# Sheet1.net
KiCad netlist of a schematic drawn in Altium Designer
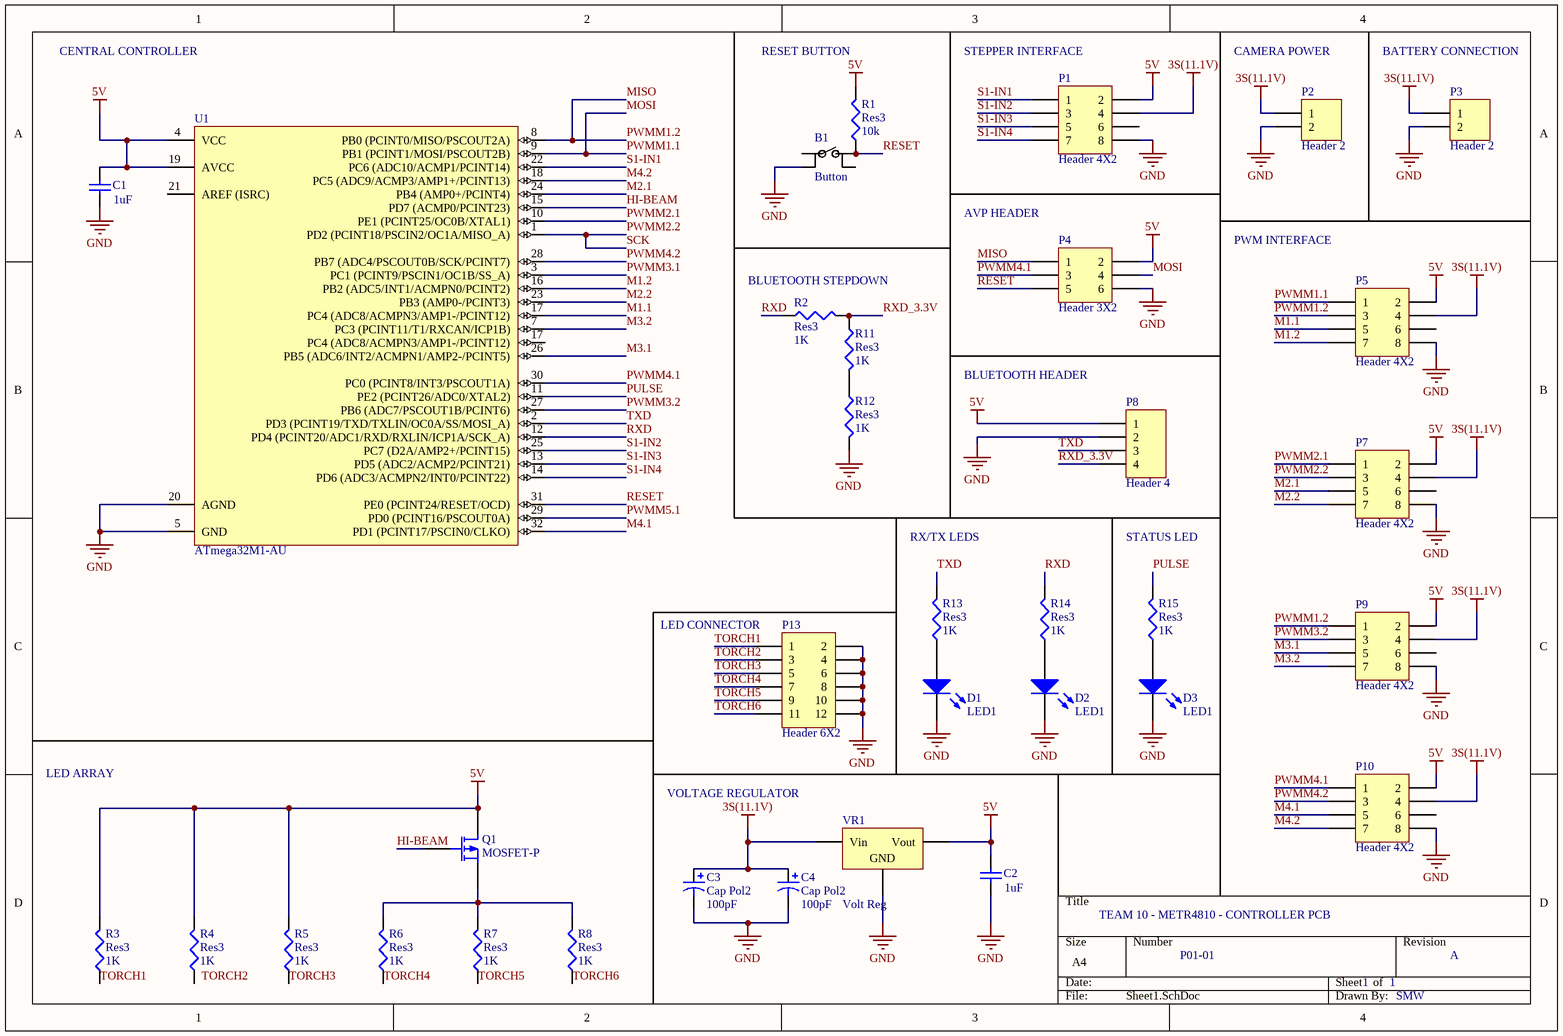
[diagram p0: Sheet1.SchDoc]

(export (version "E")
  (design (tool "Eeschema 10.0.6"))
  (components
    (comp (ref "B1")
      (value "Button")
      (footprint "SMT Tactile Button")
      (libsource (lib "WillsSchematicLibrary") (part "Switch"))
    )
    (comp (ref "C1")
      (value "1uF")
      (footprint "1608[0603]")
      (description "Capacitor")
      (fields (field (name "Comment") "Cap") (field (name "PUBLISHER") "Altium Limited"))
      (libsource (lib "Miscellaneous Devices") (part "Cap"))
    )
    (comp (ref "C2")
      (value "1uF")
      (footprint "1608[0603]")
      (description "Capacitor")
      (fields (field (name "Comment") "Cap") (field (name "PUBLISHER") "Altium Limited"))
      (libsource (lib "Miscellaneous Devices") (part "Cap"))
    )
    (comp (ref "C3")
      (value "Cap Pol2")
      (footprint "CAPAE9983X105M")
      (description "Polarized Capacitor (Axial)")
      (fields (field (name "ALTIUM_VALUE") "100pF") (field (name "PUBLISHER") "Altium Limited"))
      (libsource (lib "Miscellaneous Devices") (part "Cap Pol2"))
    )
    (comp (ref "C4")
      (value "Cap Pol2")
      (footprint "CAPAE9983X105M")
      (description "Polarized Capacitor (Axial)")
      (fields (field (name "ALTIUM_VALUE") "100pF") (field (name "PUBLISHER") "Altium Limited"))
      (libsource (lib "Miscellaneous Devices") (part "Cap Pol2"))
    )
    (comp (ref "D1")
      (value "LED1")
      (footprint "L0603")
      (description "Typical RED GaAs LED")
      (fields (field (name "PUBLISHER") "Altium Limited"))
      (libsource (lib "Miscellaneous Devices") (part "LED1"))
    )
    (comp (ref "D2")
      (value "LED1")
      (footprint "L0603")
      (description "Typical RED GaAs LED")
      (fields (field (name "PUBLISHER") "Altium Limited"))
      (libsource (lib "Miscellaneous Devices") (part "LED1"))
    )
    (comp (ref "D3")
      (value "LED1")
      (footprint "L0603")
      (description "Typical RED GaAs LED")
      (fields (field (name "PUBLISHER") "Altium Limited"))
      (libsource (lib "Miscellaneous Devices") (part "LED1"))
    )
    (comp (ref "P1")
      (value "Header 4X2")
      (footprint "HDR2X4")
      (description "Header, 4-Pin, Dual row")
      (fields (field (name "PUBLISHER") "Altium Limited"))
      (libsource (lib "Miscellaneous Connectors") (part "Header 4X2"))
    )
    (comp (ref "P2")
      (value "Header 2")
      (footprint "HDR1X2")
      (description "Header, 2-Pin")
      (fields (field (name "PUBLISHER") "Altium Limited"))
      (libsource (lib "Miscellaneous Connectors") (part "Header 2"))
    )
    (comp (ref "P3")
      (value "Header 2")
      (footprint "HDR1X2")
      (description "Header, 2-Pin")
      (fields (field (name "PUBLISHER") "Altium Limited"))
      (libsource (lib "Miscellaneous Connectors") (part "Header 2"))
    )
    (comp (ref "P4")
      (value "Header 3X2")
      (footprint "HDR2X3")
      (description "Header, 3-Pin, Dual row")
      (fields (field (name "PUBLISHER") "Altium Limited"))
      (libsource (lib "Miscellaneous Connectors") (part "Header 3X2"))
    )
    (comp (ref "P5")
      (value "Header 4X2")
      (footprint "HDR2X4")
      (description "Header, 4-Pin, Dual row")
      (fields (field (name "PUBLISHER") "Altium Limited"))
      (libsource (lib "Miscellaneous Connectors") (part "Header 4X2"))
    )
    (comp (ref "P7")
      (value "Header 4X2")
      (footprint "HDR2X4")
      (description "Header, 4-Pin, Dual row")
      (fields (field (name "PUBLISHER") "Altium Limited"))
      (libsource (lib "Miscellaneous Connectors") (part "Header 4X2"))
    )
    (comp (ref "P8")
      (value "Header 4")
      (footprint "HDR1X4")
      (description "Header, 4-Pin")
      (fields (field (name "PUBLISHER") "Altium Limited"))
      (libsource (lib "Miscellaneous Connectors") (part "Header 4"))
    )
    (comp (ref "P9")
      (value "Header 4X2")
      (footprint "HDR2X4")
      (description "Header, 4-Pin, Dual row")
      (fields (field (name "PUBLISHER") "Altium Limited"))
      (libsource (lib "Miscellaneous Connectors") (part "Header 4X2"))
    )
    (comp (ref "P10")
      (value "Header 4X2")
      (footprint "HDR2X4")
      (description "Header, 4-Pin, Dual row")
      (fields (field (name "PUBLISHER") "Altium Limited"))
      (libsource (lib "Miscellaneous Connectors") (part "Header 4X2"))
    )
    (comp (ref "P13")
      (value "Header 6X2")
      (footprint "HDR2X6")
      (description "Header, 6-Pin, Dual row")
      (fields (field (name "PUBLISHER") "Altium Limited"))
      (libsource (lib "Miscellaneous Connectors") (part "Header 6X2"))
    )
    (comp (ref "Q1")
      (value "MOSFET-P")
      (footprint "SOT23-3")
      (description "P-Channel MOSFET")
      (fields (field (name "PUBLISHER") "Altium Limited"))
      (libsource (lib "Miscellaneous Devices") (part "MOSFET-P"))
    )
    (comp (ref "R1")
      (value "Res3")
      (footprint "J1-0603")
      (description "Resistor")
      (fields (field (name "ALTIUM_VALUE") "10k") (field (name "PUBLISHER") "Altium Limited"))
      (libsource (lib "Miscellaneous Devices") (part "Res3"))
    )
    (comp (ref "R2")
      (value "Res3")
      (footprint "J1-0603")
      (description "Resistor")
      (fields (field (name "ALTIUM_VALUE") "1K") (field (name "PUBLISHER") "Altium Limited"))
      (libsource (lib "Miscellaneous Devices") (part "Res3"))
    )
    (comp (ref "R3")
      (value "Res3")
      (footprint "J1-0603")
      (description "Resistor")
      (fields (field (name "ALTIUM_VALUE") "1K") (field (name "PUBLISHER") "Altium Limited"))
      (libsource (lib "Miscellaneous Devices") (part "Res3"))
    )
    (comp (ref "R4")
      (value "Res3")
      (footprint "J1-0603")
      (description "Resistor")
      (fields (field (name "ALTIUM_VALUE") "1K") (field (name "PUBLISHER") "Altium Limited"))
      (libsource (lib "Miscellaneous Devices") (part "Res3"))
    )
    (comp (ref "R5")
      (value "Res3")
      (footprint "J1-0603")
      (description "Resistor")
      (fields (field (name "ALTIUM_VALUE") "1K") (field (name "PUBLISHER") "Altium Limited"))
      (libsource (lib "Miscellaneous Devices") (part "Res3"))
    )
    (comp (ref "R6")
      (value "Res3")
      (footprint "J1-0603")
      (description "Resistor")
      (fields (field (name "ALTIUM_VALUE") "1K") (field (name "PUBLISHER") "Altium Limited"))
      (libsource (lib "Miscellaneous Devices") (part "Res3"))
    )
    (comp (ref "R7")
      (value "Res3")
      (footprint "J1-0603")
      (description "Resistor")
      (fields (field (name "ALTIUM_VALUE") "1K") (field (name "PUBLISHER") "Altium Limited"))
      (libsource (lib "Miscellaneous Devices") (part "Res3"))
    )
    (comp (ref "R8")
      (value "Res3")
      (footprint "J1-0603")
      (description "Resistor")
      (fields (field (name "ALTIUM_VALUE") "1K") (field (name "PUBLISHER") "Altium Limited"))
      (libsource (lib "Miscellaneous Devices") (part "Res3"))
    )
    (comp (ref "R11")
      (value "Res3")
      (footprint "J1-0603")
      (description "Resistor")
      (fields (field (name "ALTIUM_VALUE") "1K") (field (name "PUBLISHER") "Altium Limited"))
      (libsource (lib "Miscellaneous Devices") (part "Res3"))
    )
    (comp (ref "R12")
      (value "Res3")
      (footprint "J1-0603")
      (description "Resistor")
      (fields (field (name "ALTIUM_VALUE") "1K") (field (name "PUBLISHER") "Altium Limited"))
      (libsource (lib "Miscellaneous Devices") (part "Res3"))
    )
    (comp (ref "R13")
      (value "Res3")
      (footprint "J1-0603")
      (description "Resistor")
      (fields (field (name "ALTIUM_VALUE") "1K") (field (name "PUBLISHER") "Altium Limited"))
      (libsource (lib "Miscellaneous Devices") (part "Res3"))
    )
    (comp (ref "R14")
      (value "Res3")
      (footprint "J1-0603")
      (description "Resistor")
      (fields (field (name "ALTIUM_VALUE") "1K") (field (name "PUBLISHER") "Altium Limited"))
      (libsource (lib "Miscellaneous Devices") (part "Res3"))
    )
    (comp (ref "R15")
      (value "Res3")
      (footprint "J1-0603")
      (description "Resistor")
      (fields (field (name "ALTIUM_VALUE") "1K") (field (name "PUBLISHER") "Altium Limited"))
      (libsource (lib "Miscellaneous Devices") (part "Res3"))
    )
    (comp (ref "U1")
      (value "ATmega32M1-AU")
      (footprint "32A_L")
      (libsource (lib "Atmel Microcontroller AVR Automotive") (part "ATmega32M1-AU"))
    )
    (comp (ref "VR1")
      (value "Volt Reg")
      (footprint "D2PAK_N")
      (description "Voltage Regulator")
      (fields (field (name "PUBLISHER") "Altium Limited"))
      (libsource (lib "Miscellaneous Devices") (part "Volt Reg"))
    )
  )
  (nets
    (net (code "1") (name "/HI-BEAM") (class "Default")
      (node (ref "Q1") (pin "2") (pinfunction "G_2") (pintype "passive"))
      (node (ref "U1") (pin "15") (pinfunction "PD7_(ACMP0/PCINT23)_15") (pintype "bidirectional"))
    )
    (net (code "2") (name "/M1.1") (class "Default")
      (node (ref "P5") (pin "5") (pinfunction "5_5") (pintype "passive"))
      (node (ref "U1") (pin "17") (pinfunction "PC4_(ADC8/ACMPN3/AMP1-/PCINT12)_17") (pintype "bidirectional"))
    )
    (net (code "3") (name "/M1.2") (class "Default")
      (node (ref "P5") (pin "7") (pinfunction "7_7") (pintype "passive"))
      (node (ref "U1") (pin "16") (pinfunction "PB2_(ADC5/INT1/ACMPN0/PCINT2)_16") (pintype "bidirectional"))
    )
    (net (code "4") (name "/M2.1") (class "Default")
      (node (ref "P7") (pin "5") (pinfunction "5_5") (pintype "passive"))
      (node (ref "U1") (pin "24") (pinfunction "PB4_(AMP0+/PCINT4)_24") (pintype "bidirectional"))
    )
    (net (code "5") (name "/M2.2") (class "Default")
      (node (ref "P7") (pin "7") (pinfunction "7_7") (pintype "passive"))
      (node (ref "U1") (pin "23") (pinfunction "PB3_(AMP0-/PCINT3)_23") (pintype "bidirectional"))
    )
    (net (code "6") (name "/M3.1") (class "Default")
      (node (ref "P9") (pin "5") (pinfunction "5_5") (pintype "passive"))
      (node (ref "U1") (pin "26") (pinfunction "PB5_(ADC6/INT2/ACMPN1/AMP2-/PCINT5)_26") (pintype "bidirectional"))
    )
    (net (code "7") (name "/M3.2") (class "Default")
      (node (ref "P9") (pin "7") (pinfunction "7_7") (pintype "passive"))
      (node (ref "U1") (pin "7") (pinfunction "PC3_(PCINT11/T1/RXCAN/ICP1B)_7") (pintype "bidirectional"))
    )
    (net (code "8") (name "/M4.1") (class "Default")
      (node (ref "P10") (pin "5") (pinfunction "5_5") (pintype "passive"))
      (node (ref "U1") (pin "32") (pinfunction "PD1_(PCINT17/PSCIN0/CLKO)_32") (pintype "bidirectional"))
    )
    (net (code "9") (name "/M4.2") (class "Default")
      (node (ref "P10") (pin "7") (pinfunction "7_7") (pintype "passive"))
      (node (ref "U1") (pin "18") (pinfunction "PC5_(ADC9/ACMP3/AMP1+/PCINT13)_18") (pintype "bidirectional"))
    )
    (net (code "10") (name "/MISO") (class "Default")
      (node (ref "P4") (pin "1") (pinfunction "1_1") (pintype "passive"))
      (node (ref "P5") (pin "3") (pinfunction "3_3") (pintype "passive"))
      (node (ref "P9") (pin "1") (pinfunction "1_1") (pintype "passive"))
      (node (ref "U1") (pin "8") (pinfunction "PB0_(PCINT0/MISO/PSCOUT2A)_8") (pintype "bidirectional"))
    )
    (net (code "11") (name "/MOSI") (class "Default")
      (node (ref "P4") (pin "4") (pinfunction "4_4") (pintype "passive"))
      (node (ref "P5") (pin "1") (pinfunction "1_1") (pintype "passive"))
      (node (ref "U1") (pin "9") (pinfunction "PB1_(PCINT1/MOSI/PSCOUT2B)_9") (pintype "bidirectional"))
    )
    (net (code "12") (name "/PULSE") (class "Default")
      (node (ref "R15") (pin "2") (pinfunction "2_2") (pintype "passive"))
      (node (ref "U1") (pin "11") (pinfunction "PE2_(PCINT26/ADC0/XTAL2)_11") (pintype "bidirectional"))
    )
    (net (code "13") (name "/PWMM2.1") (class "Default")
      (node (ref "P7") (pin "1") (pinfunction "1_1") (pintype "passive"))
      (node (ref "U1") (pin "10") (pinfunction "PE1_(PCINT25/OC0B/XTAL1)_10") (pintype "bidirectional"))
    )
    (net (code "14") (name "/PWMM2.2") (class "Default")
      (node (ref "P7") (pin "3") (pinfunction "3_3") (pintype "passive"))
      (node (ref "U1") (pin "1") (pinfunction "PD2_(PCINT18/PSCIN2/OC1A/MISO_A)_1") (pintype "bidirectional"))
    )
    (net (code "15") (name "/PWMM3.1") (class "Default")
      (node (ref "U1") (pin "3") (pinfunction "PC1_(PCINT9/PSCIN1/OC1B/SS_A)_3") (pintype "bidirectional"))
    )
    (net (code "16") (name "/PWMM3.2") (class "Default")
      (node (ref "P9") (pin "3") (pinfunction "3_3") (pintype "passive"))
      (node (ref "U1") (pin "27") (pinfunction "PB6_(ADC7/PSCOUT1B/PCINT6)_27") (pintype "bidirectional"))
    )
    (net (code "17") (name "/PWMM4.1") (class "Default")
      (node (ref "P10") (pin "1") (pinfunction "1_1") (pintype "passive"))
      (node (ref "P4") (pin "3") (pinfunction "3_3") (pintype "passive"))
      (node (ref "U1") (pin "30") (pinfunction "PC0_(PCINT8/INT3/PSCOUT1A)_30") (pintype "bidirectional"))
    )
    (net (code "18") (name "/PWMM4.2") (class "Default")
      (node (ref "P10") (pin "3") (pinfunction "3_3") (pintype "passive"))
      (node (ref "U1") (pin "28") (pinfunction "PB7_(ADC4/PSCOUT0B/SCK/PCINT7)_28") (pintype "bidirectional"))
    )
    (net (code "19") (name "/PWMM5.1") (class "Default")
      (node (ref "U1") (pin "29") (pinfunction "PD0_(PCINT16/PSCOUT0A)_29") (pintype "bidirectional"))
    )
    (net (code "20") (name "/RESET") (class "Default")
      (node (ref "B1") (pin "4") (pinfunction "4_4") (pintype "passive"))
      (node (ref "P4") (pin "5") (pinfunction "5_5") (pintype "passive"))
      (node (ref "R1") (pin "1") (pinfunction "1_1") (pintype "passive"))
      (node (ref "U1") (pin "31") (pinfunction "PE0_(PCINT24/RESET/OCD)_31") (pintype "bidirectional"))
    )
    (net (code "21") (name "/RXD") (class "Default")
      (node (ref "R14") (pin "2") (pinfunction "2_2") (pintype "passive"))
      (node (ref "R2") (pin "1") (pinfunction "1_1") (pintype "passive"))
      (node (ref "U1") (pin "12") (pinfunction "PD4_(PCINT20/ADC1/RXD/RXLIN/ICP1A/SCK_A)_12") (pintype "bidirectional"))
    )
    (net (code "22") (name "/RXD_3.3V") (class "Default")
      (node (ref "P8") (pin "4") (pinfunction "4_4") (pintype "passive"))
      (node (ref "R11") (pin "1") (pinfunction "1_1") (pintype "passive"))
      (node (ref "R2") (pin "2") (pinfunction "2_2") (pintype "passive"))
    )
    (net (code "23") (name "/S1-IN1") (class "Default")
      (node (ref "P1") (pin "1") (pinfunction "1_1") (pintype "passive"))
      (node (ref "U1") (pin "22") (pinfunction "PC6_(ADC10/ACMP1/PCINT14)_22") (pintype "bidirectional"))
    )
    (net (code "24") (name "/S1-IN2") (class "Default")
      (node (ref "P1") (pin "3") (pinfunction "3_3") (pintype "passive"))
      (node (ref "U1") (pin "25") (pinfunction "PC7_(D2A/AMP2+/PCINT15)_25") (pintype "bidirectional"))
    )
    (net (code "25") (name "/S1-IN3") (class "Default")
      (node (ref "P1") (pin "5") (pinfunction "5_5") (pintype "passive"))
      (node (ref "U1") (pin "13") (pinfunction "PD5_(ADC2/ACMP2/PCINT21)_13") (pintype "bidirectional"))
    )
    (net (code "26") (name "/S1-IN4") (class "Default")
      (node (ref "P1") (pin "7") (pinfunction "7_7") (pintype "passive"))
      (node (ref "U1") (pin "14") (pinfunction "PD6_(ADC3/ACMPN2/INT0/PCINT22)_14") (pintype "bidirectional"))
    )
    (net (code "27") (name "/TORCH1") (class "Default")
      (node (ref "P13") (pin "1") (pinfunction "1_1") (pintype "passive"))
      (node (ref "R3") (pin "1") (pinfunction "1_1") (pintype "passive"))
    )
    (net (code "28") (name "/TORCH2") (class "Default")
      (node (ref "P13") (pin "3") (pinfunction "3_3") (pintype "passive"))
    )
    (net (code "29") (name "/TORCH3") (class "Default")
      (node (ref "P13") (pin "5") (pinfunction "5_5") (pintype "passive"))
      (node (ref "R5") (pin "1") (pinfunction "1_1") (pintype "passive"))
    )
    (net (code "30") (name "/TORCH4") (class "Default")
      (node (ref "P13") (pin "7") (pinfunction "7_7") (pintype "passive"))
      (node (ref "R6") (pin "1") (pinfunction "1_1") (pintype "passive"))
    )
    (net (code "31") (name "/TORCH5") (class "Default")
      (node (ref "P13") (pin "9") (pinfunction "9_9") (pintype "passive"))
      (node (ref "R7") (pin "1") (pinfunction "1_1") (pintype "passive"))
    )
    (net (code "32") (name "/TORCH6") (class "Default")
      (node (ref "P13") (pin "11") (pinfunction "11_11") (pintype "passive"))
      (node (ref "R8") (pin "1") (pinfunction "1_1") (pintype "passive"))
    )
    (net (code "33") (name "/TXD") (class "Default")
      (node (ref "P8") (pin "3") (pinfunction "3_3") (pintype "passive"))
      (node (ref "R13") (pin "2") (pinfunction "2_2") (pintype "passive"))
      (node (ref "U1") (pin "2") (pinfunction "PD3_(PCINT19/TXD/TXLIN/OC0A/SS/MOSI_A)_2") (pintype "bidirectional"))
    )
    (net (code "34") (name "3S(11.1V)") (class "Default")
      (node (ref "C3") (pin "1") (pinfunction "1_1") (pintype "passive"))
      (node (ref "C4") (pin "1") (pinfunction "1_1") (pintype "passive"))
      (node (ref "P1") (pin "4") (pinfunction "4_4") (pintype "passive"))
      (node (ref "P10") (pin "4") (pinfunction "4_4") (pintype "passive"))
      (node (ref "P2") (pin "1") (pinfunction "1_1") (pintype "passive"))
      (node (ref "P3") (pin "1") (pinfunction "1_1") (pintype "passive"))
      (node (ref "P5") (pin "4") (pinfunction "4_4") (pintype "passive"))
      (node (ref "P7") (pin "4") (pinfunction "4_4") (pintype "passive"))
      (node (ref "P9") (pin "4") (pinfunction "4_4") (pintype "passive"))
      (node (ref "VR1") (pin "1") (pinfunction "Vin_1") (pintype "passive"))
    )
    (net (code "35") (name "5V") (class "Default")
      (node (ref "C1") (pin "2") (pinfunction "2_2") (pintype "passive"))
      (node (ref "C2") (pin "2") (pinfunction "2_2") (pintype "passive"))
      (node (ref "P1") (pin "2") (pinfunction "2_2") (pintype "passive"))
      (node (ref "P10") (pin "2") (pinfunction "2_2") (pintype "passive"))
      (node (ref "P4") (pin "2") (pinfunction "2_2") (pintype "passive"))
      (node (ref "P5") (pin "2") (pinfunction "2_2") (pintype "passive"))
      (node (ref "P7") (pin "2") (pinfunction "2_2") (pintype "passive"))
      (node (ref "P8") (pin "1") (pinfunction "1_1") (pintype "passive"))
      (node (ref "P9") (pin "2") (pinfunction "2_2") (pintype "passive"))
      (node (ref "Q1") (pin "1") (pinfunction "D_1") (pintype "passive"))
      (node (ref "R1") (pin "2") (pinfunction "2_2") (pintype "passive"))
      (node (ref "R3") (pin "2") (pinfunction "2_2") (pintype "passive"))
      (node (ref "R4") (pin "2") (pinfunction "2_2") (pintype "passive"))
      (node (ref "R5") (pin "2") (pinfunction "2_2") (pintype "passive"))
      (node (ref "U1") (pin "19") (pinfunction "AVCC_19") (pintype "power_in"))
      (node (ref "U1") (pin "4") (pinfunction "VCC_4") (pintype "power_in"))
      (node (ref "VR1") (pin "3") (pinfunction "Vout_3") (pintype "passive"))
    )
    (net (code "36") (name "GND") (class "Default")
      (node (ref "B1") (pin "2") (pinfunction "2_2") (pintype "passive"))
      (node (ref "C1") (pin "1") (pinfunction "1_1") (pintype "passive"))
      (node (ref "C2") (pin "1") (pinfunction "1_1") (pintype "passive"))
      (node (ref "C3") (pin "2") (pinfunction "2_2") (pintype "passive"))
      (node (ref "C4") (pin "2") (pinfunction "2_2") (pintype "passive"))
      (node (ref "D1") (pin "2") (pinfunction "K_2") (pintype "passive"))
      (node (ref "D2") (pin "2") (pinfunction "K_2") (pintype "passive"))
      (node (ref "D3") (pin "2") (pinfunction "K_2") (pintype "passive"))
      (node (ref "P1") (pin "8") (pinfunction "8_8") (pintype "passive"))
      (node (ref "P10") (pin "8") (pinfunction "8_8") (pintype "passive"))
      (node (ref "P13") (pin "10") (pinfunction "10_10") (pintype "passive"))
      (node (ref "P13") (pin "12") (pinfunction "12_12") (pintype "passive"))
      (node (ref "P13") (pin "2") (pinfunction "2_2") (pintype "passive"))
      (node (ref "P13") (pin "4") (pinfunction "4_4") (pintype "passive"))
      (node (ref "P13") (pin "6") (pinfunction "6_6") (pintype "passive"))
      (node (ref "P13") (pin "8") (pinfunction "8_8") (pintype "passive"))
      (node (ref "P2") (pin "2") (pinfunction "2_2") (pintype "passive"))
      (node (ref "P3") (pin "2") (pinfunction "2_2") (pintype "passive"))
      (node (ref "P4") (pin "6") (pinfunction "6_6") (pintype "passive"))
      (node (ref "P5") (pin "8") (pinfunction "8_8") (pintype "passive"))
      (node (ref "P7") (pin "8") (pinfunction "8_8") (pintype "passive"))
      (node (ref "P8") (pin "2") (pinfunction "2_2") (pintype "passive"))
      (node (ref "P9") (pin "8") (pinfunction "8_8") (pintype "passive"))
      (node (ref "R12") (pin "2") (pinfunction "2_2") (pintype "passive"))
      (node (ref "U1") (pin "20") (pinfunction "AGND_20") (pintype "power_in"))
      (node (ref "U1") (pin "5") (pinfunction "GND_5") (pintype "power_in"))
      (node (ref "VR1") (pin "2") (pinfunction "GND_2") (pintype "passive"))
    )
    (net (code "37") (name "Net-(D1-A)") (class "Default")
      (node (ref "D1") (pin "1") (pinfunction "A_1") (pintype "passive"))
      (node (ref "R13") (pin "1") (pinfunction "1_1") (pintype "passive"))
    )
    (net (code "38") (name "Net-(D2-A)") (class "Default")
      (node (ref "D2") (pin "1") (pinfunction "A_1") (pintype "passive"))
      (node (ref "R14") (pin "1") (pinfunction "1_1") (pintype "passive"))
    )
    (net (code "39") (name "Net-(D3-A)") (class "Default")
      (node (ref "D3") (pin "1") (pinfunction "A_1") (pintype "passive"))
      (node (ref "R15") (pin "1") (pinfunction "1_1") (pintype "passive"))
    )
    (net (code "40") (name "Net-(Q1-S)") (class "Default")
      (node (ref "Q1") (pin "3") (pinfunction "S_3") (pintype "passive"))
      (node (ref "R6") (pin "2") (pinfunction "2_2") (pintype "passive"))
      (node (ref "R7") (pin "2") (pinfunction "2_2") (pintype "passive"))
      (node (ref "R8") (pin "2") (pinfunction "2_2") (pintype "passive"))
    )
    (net (code "41") (name "Net-(R11-Pad2)") (class "Default")
      (node (ref "R11") (pin "2") (pinfunction "2_2") (pintype "passive"))
      (node (ref "R12") (pin "1") (pinfunction "1_1") (pintype "passive"))
    )
    (net (code "42") (name "unconnected-(B1-Pad1)") (class "Default")
      (node (ref "B1") (pin "1") (pinfunction "1_1") (pintype "passive"))
    )
    (net (code "43") (name "unconnected-(B1-Pad3)") (class "Default")
      (node (ref "B1") (pin "3") (pinfunction "3_3") (pintype "passive"))
    )
    (net (code "44") (name "unconnected-(P1-Pad6)") (class "Default")
      (node (ref "P1") (pin "6") (pinfunction "6_6") (pintype "passive"))
    )
    (net (code "45") (name "unconnected-(P5-Pad6)") (class "Default")
      (node (ref "P5") (pin "6") (pinfunction "6_6") (pintype "passive"))
    )
    (net (code "46") (name "unconnected-(P7-Pad6)") (class "Default")
      (node (ref "P7") (pin "6") (pinfunction "6_6") (pintype "passive"))
    )
    (net (code "47") (name "unconnected-(P9-Pad6)") (class "Default")
      (node (ref "P9") (pin "6") (pinfunction "6_6") (pintype "passive"))
    )
    (net (code "48") (name "unconnected-(P10-Pad6)") (class "Default")
      (node (ref "P10") (pin "6") (pinfunction "6_6") (pintype "passive"))
    )
    (net (code "49") (name "unconnected-(R4-Pad1)") (class "Default")
      (node (ref "R4") (pin "1") (pinfunction "1_1") (pintype "passive"))
    )
    (net (code "50") (name "unconnected-(U1-AREF_(ISRC)-Pad21)") (class "Default")
      (node (ref "U1") (pin "21") (pinfunction "AREF_(ISRC)_21") (pintype "power_in"))
    )
    (net (code "51") (name "unconnected-(U1-PC4_(ADC8{slash}ACMPN3{slash}AMP1-{slash}PCINT12)-Pad17)") (class "Default")
      (node (ref "U1") (pin "17") (pinfunction "PC4_(ADC8/ACMPN3/AMP1-/PCINT12)_17") (pintype "bidirectional"))
    )
  )
)
